# micro_board.net
KiCad netlist of a schematic drawn in EAGLE
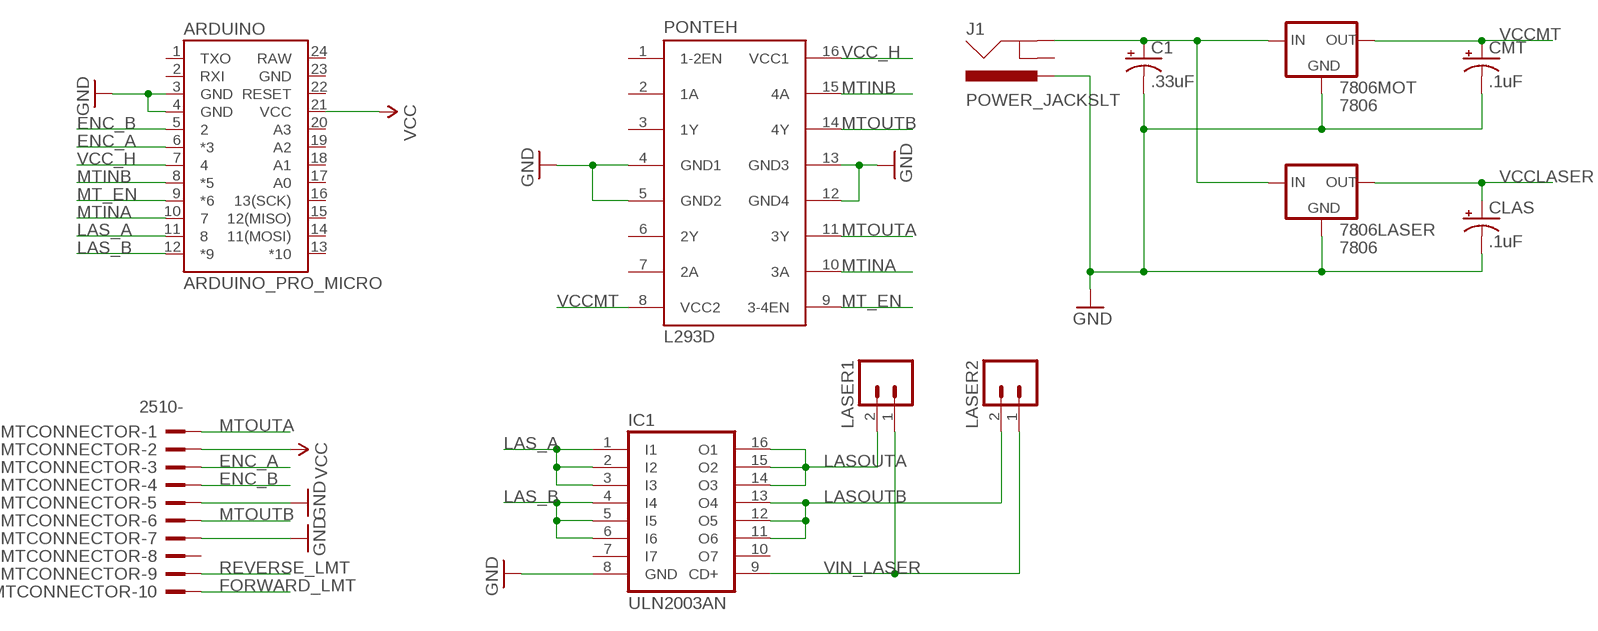
[diagram p0: schematic, sheet 1]

(export (version "E")
  (design (tool "Eeschema 10.0.6"))
  (components
    (comp (ref "7806LASER")
      (value "7806")
      (footprint "eagle-import:TO220-IGO")
      (libsource (lib "eagle-import") (part "V_REG_78XXSINK"))
    )
    (comp (ref "7806MOT")
      (value "7806")
      (footprint "eagle-import:TO220-IGO")
      (libsource (lib "eagle-import") (part "V_REG_78XXSINK"))
    )
    (comp (ref "ARDUINO")
      (value "ARDUINO_PRO_MICRO")
      (footprint "eagle-import:ARDUINO_PRO_MICRO")
      (libsource (lib "eagle-import") (part "ARDUINO_PRO_MICRO"))
    )
    (comp (ref "C1")
      (value ".33uF")
      (footprint "eagle-import:CPOL-RADIAL-100UF-25V")
      (libsource (lib "eagle-import") (part "CAP_POLPTH1"))
    )
    (comp (ref "CLAS")
      (value ".1uF")
      (footprint "eagle-import:CPOL-RADIAL-100UF-25V")
      (libsource (lib "eagle-import") (part "CAP_POLPTH1"))
    )
    (comp (ref "CMT")
      (value ".1uF")
      (footprint "eagle-import:CPOL-RADIAL-100UF-25V")
      (libsource (lib "eagle-import") (part "CAP_POLPTH1"))
    )
    (comp (ref "IC1")
      (value "ULN2003AN")
      (footprint "eagle-import:DIL16")
      (libsource (lib "eagle-import") (part "ULN2003AN"))
    )
    (comp (ref "J1")
      (value "POWER_JACKSLT")
      (footprint "eagle-import:POWER_JACK_SLOT")
      (libsource (lib "eagle-import") (part "POWER_JACKSLT"))
    )
    (comp (ref "LASER1")
      (value "M02POLAR")
      (footprint "eagle-import:MOLEX-1X2")
      (libsource (lib "eagle-import") (part "M02POLAR"))
    )
    (comp (ref "LASER2")
      (value "M02POLAR")
      (footprint "eagle-import:MOLEX-1X2")
      (libsource (lib "eagle-import") (part "M02POLAR"))
    )
    (comp (ref "MTCONNECTOR")
      (value "2510-")
      (footprint "eagle-import:PAK100_2500-10")
      (fields (field (name "MF") "3M") (field (name "MPN") "2510-6002UB"))
      (libsource (lib "eagle-import") (part "2510-"))
    )
    (comp (ref "PONTEH")
      (value "L293D")
      (footprint "eagle-import:DIL16")
      (libsource (lib "eagle-import") (part "L293D"))
    )
  )
  (nets
    (net (code "1") (name "/ENC_A") (class "Default")
      (node (ref "ARDUINO") (pin "6") (pinfunction "*3_6") (pintype "bidirectional"))
      (node (ref "MTCONNECTOR") (pin "3") (pinfunction "KL_3") (pintype "passive"))
    )
    (net (code "2") (name "/ENC_B") (class "Default")
      (node (ref "ARDUINO") (pin "5") (pinfunction "2_5") (pintype "bidirectional"))
      (node (ref "MTCONNECTOR") (pin "4") (pinfunction "KL_4") (pintype "passive"))
    )
    (net (code "3") (name "/FORWARD_LMT") (class "Default")
      (node (ref "MTCONNECTOR") (pin "10") (pinfunction "KL_10") (pintype "passive"))
    )
    (net (code "4") (name "/LASOUTA") (class "Default")
      (node (ref "IC1") (pin "14") (pinfunction "O3_14") (pintype "open_collector"))
      (node (ref "IC1") (pin "15") (pinfunction "O2_15") (pintype "open_collector"))
      (node (ref "IC1") (pin "16") (pinfunction "O1_16") (pintype "open_collector"))
      (node (ref "LASER1") (pin "2") (pinfunction "2_2") (pintype "passive"))
    )
    (net (code "5") (name "/LASOUTB") (class "Default")
      (node (ref "IC1") (pin "11") (pinfunction "O6_11") (pintype "open_collector"))
      (node (ref "IC1") (pin "12") (pinfunction "O5_12") (pintype "open_collector"))
      (node (ref "IC1") (pin "13") (pinfunction "O4_13") (pintype "open_collector"))
      (node (ref "LASER2") (pin "2") (pinfunction "2_2") (pintype "passive"))
    )
    (net (code "6") (name "/LAS_A") (class "Default")
      (node (ref "ARDUINO") (pin "11") (pinfunction "8_11") (pintype "bidirectional"))
      (node (ref "IC1") (pin "1") (pinfunction "I1_1") (pintype "input"))
      (node (ref "IC1") (pin "2") (pinfunction "I2_2") (pintype "input"))
      (node (ref "IC1") (pin "3") (pinfunction "I3_3") (pintype "input"))
    )
    (net (code "7") (name "/LAS_B") (class "Default")
      (node (ref "ARDUINO") (pin "12") (pinfunction "*9_12") (pintype "bidirectional"))
      (node (ref "IC1") (pin "4") (pinfunction "I4_4") (pintype "input"))
      (node (ref "IC1") (pin "5") (pinfunction "I5_5") (pintype "input"))
      (node (ref "IC1") (pin "6") (pinfunction "I6_6") (pintype "input"))
    )
    (net (code "8") (name "/MTINA") (class "Default")
      (node (ref "ARDUINO") (pin "10") (pinfunction "7_10") (pintype "bidirectional"))
      (node (ref "PONTEH") (pin "10") (pinfunction "3A_10") (pintype "input"))
    )
    (net (code "9") (name "/MTINB") (class "Default")
      (node (ref "ARDUINO") (pin "8") (pinfunction "*5_8") (pintype "bidirectional"))
      (node (ref "PONTEH") (pin "15") (pinfunction "4A_15") (pintype "input"))
    )
    (net (code "10") (name "/MTOUTA") (class "Default")
      (node (ref "MTCONNECTOR") (pin "1") (pinfunction "KL_1") (pintype "passive"))
      (node (ref "PONTEH") (pin "11") (pinfunction "3Y_11") (pintype "output"))
    )
    (net (code "11") (name "/MTOUTB") (class "Default")
      (node (ref "MTCONNECTOR") (pin "6") (pinfunction "KL_6") (pintype "passive"))
      (node (ref "PONTEH") (pin "14") (pinfunction "4Y_14") (pintype "output"))
    )
    (net (code "12") (name "/MT_EN") (class "Default")
      (node (ref "ARDUINO") (pin "9") (pinfunction "*6_9") (pintype "bidirectional"))
      (node (ref "PONTEH") (pin "9") (pinfunction "3-4EN_9") (pintype "input"))
    )
    (net (code "13") (name "/REVERSE_LMT") (class "Default")
      (node (ref "MTCONNECTOR") (pin "9") (pinfunction "KL_9") (pintype "passive"))
    )
    (net (code "14") (name "/VCCLASER") (class "Default")
      (node (ref "7806LASER") (pin "OUT") (pinfunction "OUT_OUT") (pintype "passive"))
      (node (ref "CLAS") (pin "1") (pinfunction "+_1") (pintype "passive"))
    )
    (net (code "15") (name "/VCCMT") (class "Default")
      (node (ref "7806MOT") (pin "OUT") (pinfunction "OUT_OUT") (pintype "passive"))
      (node (ref "CMT") (pin "1") (pinfunction "+_1") (pintype "passive"))
      (node (ref "PONTEH") (pin "8") (pinfunction "VCC2_8") (pintype "power_in"))
    )
    (net (code "16") (name "/VCC_H") (class "Default")
      (node (ref "ARDUINO") (pin "7") (pinfunction "4_7") (pintype "bidirectional"))
      (node (ref "PONTEH") (pin "16") (pinfunction "VCC1_16") (pintype "power_in"))
    )
    (net (code "17") (name "/VIN_LASER") (class "Default")
      (node (ref "IC1") (pin "9") (pinfunction "CD+_9") (pintype "passive"))
      (node (ref "LASER1") (pin "1") (pinfunction "1_1") (pintype "passive"))
      (node (ref "LASER2") (pin "1") (pinfunction "1_1") (pintype "passive"))
    )
    (net (code "18") (name "GND") (class "Default")
      (node (ref "7806LASER") (pin "GND") (pinfunction "GND_GND") (pintype "input"))
      (node (ref "7806MOT") (pin "GND") (pinfunction "GND_GND") (pintype "input"))
      (node (ref "ARDUINO") (pin "3") (pinfunction "GND_3") (pintype "bidirectional"))
      (node (ref "ARDUINO") (pin "4") (pinfunction "GND_4") (pintype "bidirectional"))
      (node (ref "C1") (pin "2") (pinfunction "-_2") (pintype "passive"))
      (node (ref "CLAS") (pin "2") (pinfunction "-_2") (pintype "passive"))
      (node (ref "CMT") (pin "2") (pinfunction "-_2") (pintype "passive"))
      (node (ref "IC1") (pin "8") (pinfunction "GND_8") (pintype "power_in"))
      (node (ref "J1") (pin "PWR") (pinfunction "PWR_PWR") (pintype "bidirectional"))
      (node (ref "MTCONNECTOR") (pin "5") (pinfunction "KL_5") (pintype "passive"))
      (node (ref "MTCONNECTOR") (pin "7") (pinfunction "KL_7") (pintype "passive"))
      (node (ref "PONTEH") (pin "12") (pinfunction "GND4_12") (pintype "power_in"))
      (node (ref "PONTEH") (pin "13") (pinfunction "GND3_13") (pintype "power_in"))
      (node (ref "PONTEH") (pin "4") (pinfunction "GND1_4") (pintype "power_in"))
      (node (ref "PONTEH") (pin "5") (pinfunction "GND2_5") (pintype "power_in"))
    )
    (net (code "19") (name "Net-(C1-+)") (class "Default")
      (node (ref "7806LASER") (pin "IN") (pinfunction "IN_IN") (pintype "input"))
      (node (ref "7806MOT") (pin "IN") (pinfunction "IN_IN") (pintype "input"))
      (node (ref "C1") (pin "1") (pinfunction "+_1") (pintype "passive"))
      (node (ref "J1") (pin "GND@2") (pinfunction "GND_GND@2") (pintype "bidirectional"))
    )
    (net (code "20") (name "VCC") (class "Default")
      (node (ref "ARDUINO") (pin "21") (pinfunction "VCC_21") (pintype "bidirectional"))
      (node (ref "MTCONNECTOR") (pin "2") (pinfunction "KL_2") (pintype "passive"))
    )
    (net (code "21") (name "unconnected-(ARDUINO-*10-Pad13)") (class "Default")
      (node (ref "ARDUINO") (pin "13") (pinfunction "*10_13") (pintype "bidirectional"))
    )
    (net (code "22") (name "unconnected-(ARDUINO-11(MOSI)-Pad14)") (class "Default")
      (node (ref "ARDUINO") (pin "14") (pinfunction "11(MOSI)_14") (pintype "bidirectional"))
    )
    (net (code "23") (name "unconnected-(ARDUINO-12(MISO)-Pad15)") (class "Default")
      (node (ref "ARDUINO") (pin "15") (pinfunction "12(MISO)_15") (pintype "bidirectional"))
    )
    (net (code "24") (name "unconnected-(ARDUINO-13(SCK)-Pad16)") (class "Default")
      (node (ref "ARDUINO") (pin "16") (pinfunction "13(SCK)_16") (pintype "bidirectional"))
    )
    (net (code "25") (name "unconnected-(ARDUINO-A0-Pad17)") (class "Default")
      (node (ref "ARDUINO") (pin "17") (pinfunction "A0_17") (pintype "bidirectional"))
    )
    (net (code "26") (name "unconnected-(ARDUINO-A1-Pad18)") (class "Default")
      (node (ref "ARDUINO") (pin "18") (pinfunction "A1_18") (pintype "bidirectional"))
    )
    (net (code "27") (name "unconnected-(ARDUINO-A2-Pad19)") (class "Default")
      (node (ref "ARDUINO") (pin "19") (pinfunction "A2_19") (pintype "bidirectional"))
    )
    (net (code "28") (name "unconnected-(ARDUINO-A3-Pad20)") (class "Default")
      (node (ref "ARDUINO") (pin "20") (pinfunction "A3_20") (pintype "bidirectional"))
    )
    (net (code "29") (name "unconnected-(ARDUINO-GND-Pad23)") (class "Default")
      (node (ref "ARDUINO") (pin "23") (pinfunction "GND_23") (pintype "bidirectional"))
    )
    (net (code "30") (name "unconnected-(ARDUINO-RAW-Pad24)") (class "Default")
      (node (ref "ARDUINO") (pin "24") (pinfunction "RAW_24") (pintype "bidirectional"))
    )
    (net (code "31") (name "unconnected-(ARDUINO-RESET-Pad22)") (class "Default")
      (node (ref "ARDUINO") (pin "22") (pinfunction "RESET_22") (pintype "bidirectional"))
    )
    (net (code "32") (name "unconnected-(ARDUINO-RXI-Pad2)") (class "Default")
      (node (ref "ARDUINO") (pin "2") (pinfunction "RXI_2") (pintype "bidirectional"))
    )
    (net (code "33") (name "unconnected-(ARDUINO-TXO-Pad1)") (class "Default")
      (node (ref "ARDUINO") (pin "1") (pinfunction "TXO_1") (pintype "bidirectional"))
    )
    (net (code "34") (name "unconnected-(IC1-I7-Pad7)") (class "Default")
      (node (ref "IC1") (pin "7") (pinfunction "I7_7") (pintype "input"))
    )
    (net (code "35") (name "unconnected-(IC1-O7-Pad10)") (class "Default")
      (node (ref "IC1") (pin "10") (pinfunction "O7_10") (pintype "open_collector"))
    )
    (net (code "36") (name "unconnected-(J1-GNDBREAK-PadGND@1)") (class "Default")
      (node (ref "J1") (pin "GND@1") (pinfunction "GNDBREAK_GND@1") (pintype "bidirectional"))
    )
    (net (code "37") (name "unconnected-(MTCONNECTORI-KL-Pad8)") (class "Default")
      (node (ref "MTCONNECTOR") (pin "8") (pinfunction "KL_8") (pintype "passive"))
    )
    (net (code "38") (name "unconnected-(PONTEH-1-2EN-Pad1)") (class "Default")
      (node (ref "PONTEH") (pin "1") (pinfunction "1-2EN_1") (pintype "input"))
    )
    (net (code "39") (name "unconnected-(PONTEH-1A-Pad2)") (class "Default")
      (node (ref "PONTEH") (pin "2") (pinfunction "1A_2") (pintype "input"))
    )
    (net (code "40") (name "unconnected-(PONTEH-1Y-Pad3)") (class "Default")
      (node (ref "PONTEH") (pin "3") (pinfunction "1Y_3") (pintype "output"))
    )
    (net (code "41") (name "unconnected-(PONTEH-2A-Pad7)") (class "Default")
      (node (ref "PONTEH") (pin "7") (pinfunction "2A_7") (pintype "input"))
    )
    (net (code "42") (name "unconnected-(PONTEH-2Y-Pad6)") (class "Default")
      (node (ref "PONTEH") (pin "6") (pinfunction "2Y_6") (pintype "output"))
    )
  )
)
